# Top.net
KiCad netlist of a schematic drawn in Altium Designer
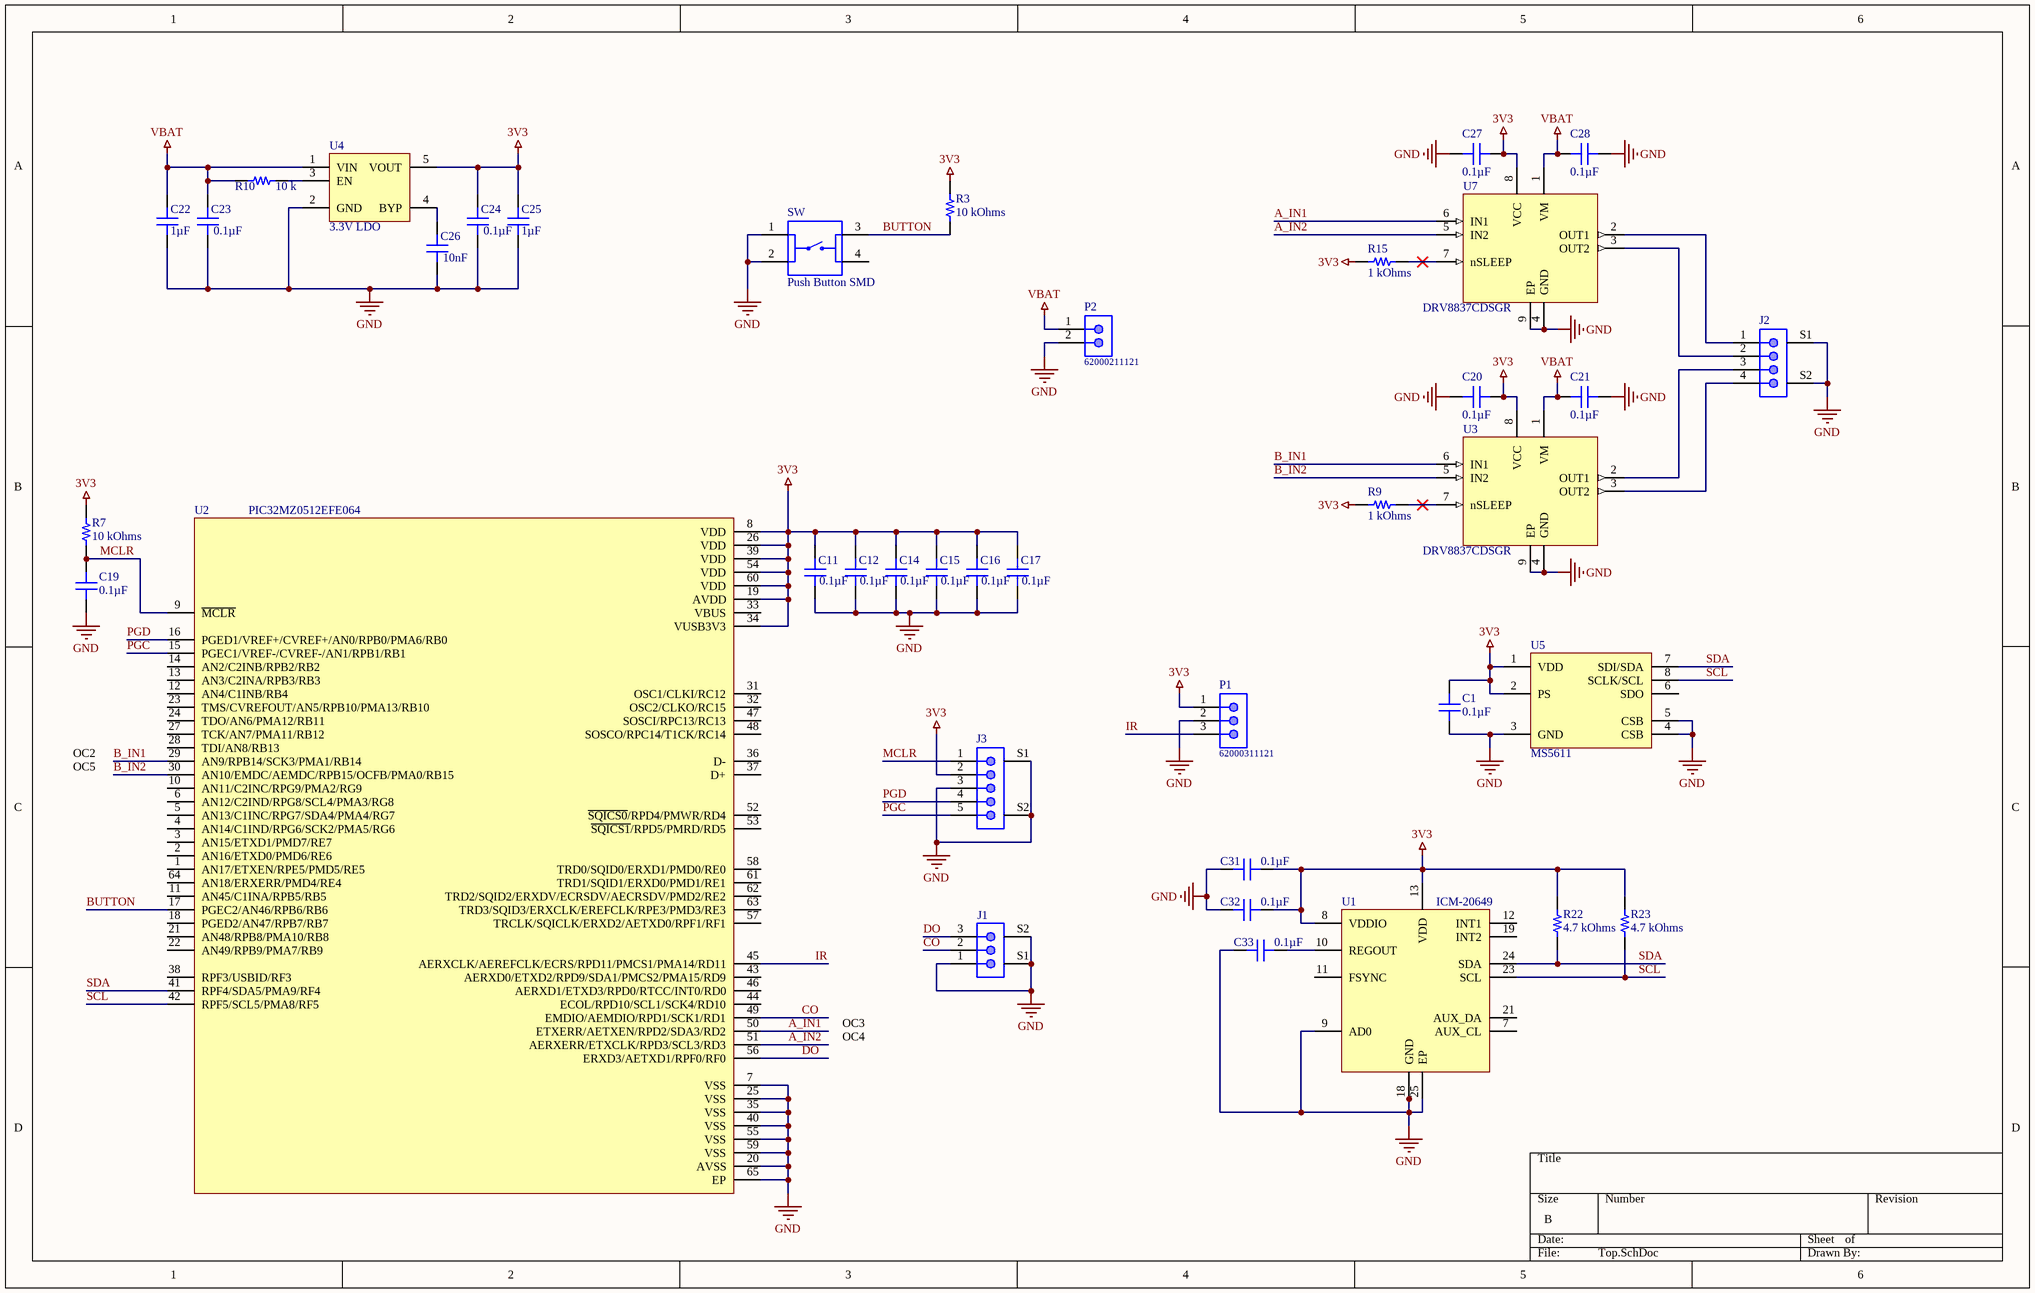
[diagram p0: Top.SchDoc]

(export (version "E")
  (design (tool "Eeschema 10.0.6"))
  (components
    (comp (ref "C1")
      (value "0.1µF")
      (footprint "CAP 0603_1608")
      (description "CAP CER 0.1UF 100V 0603 EPOXY")
      (fields
        (field (name "PART NUMBER") "GCG188R92A104KA03D")
        (field (name "MANUFACTURER") "Murata Electronics")
      )
      (libsource (lib "Celestial Altium Library - altium_library") (part "Capacitor"))
    )
    (comp (ref "C11")
      (value "0.1µF")
      (footprint "CAP 0603_1608")
      (description "CAP CER 0.1UF 100V 0603 EPOXY")
      (fields
        (field (name "PART NUMBER") "GCG188R92A104KA03D")
        (field (name "MANUFACTURER") "Murata Electronics")
      )
      (libsource (lib "Celestial Altium Library - altium_library") (part "Capacitor"))
    )
    (comp (ref "C12")
      (value "0.1µF")
      (footprint "CAP 0603_1608")
      (description "CAP CER 0.1UF 100V 0603 EPOXY")
      (fields
        (field (name "PART NUMBER") "GCG188R92A104KA03D")
        (field (name "MANUFACTURER") "Murata Electronics")
      )
      (libsource (lib "Celestial Altium Library - altium_library") (part "Capacitor"))
    )
    (comp (ref "C14")
      (value "0.1µF")
      (footprint "CAP 0603_1608")
      (description "CAP CER 0.1UF 100V 0603 EPOXY")
      (fields
        (field (name "PART NUMBER") "GCG188R92A104KA03D")
        (field (name "MANUFACTURER") "Murata Electronics")
      )
      (libsource (lib "Celestial Altium Library - altium_library") (part "Capacitor"))
    )
    (comp (ref "C15")
      (value "0.1µF")
      (footprint "CAP 0603_1608")
      (description "CAP CER 0.1UF 100V 0603 EPOXY")
      (fields
        (field (name "PART NUMBER") "GCG188R92A104KA03D")
        (field (name "MANUFACTURER") "Murata Electronics")
      )
      (libsource (lib "Celestial Altium Library - altium_library") (part "Capacitor"))
    )
    (comp (ref "C16")
      (value "0.1µF")
      (footprint "CAP 0603_1608")
      (description "CAP CER 0.1UF 100V 0603 EPOXY")
      (fields
        (field (name "PART NUMBER") "GCG188R92A104KA03D")
        (field (name "MANUFACTURER") "Murata Electronics")
      )
      (libsource (lib "Celestial Altium Library - altium_library") (part "Capacitor"))
    )
    (comp (ref "C17")
      (value "0.1µF")
      (footprint "CAP 0603_1608")
      (description "CAP CER 0.1UF 100V 0603 EPOXY")
      (fields
        (field (name "PART NUMBER") "GCG188R92A104KA03D")
        (field (name "MANUFACTURER") "Murata Electronics")
      )
      (libsource (lib "Celestial Altium Library - altium_library") (part "Capacitor"))
    )
    (comp (ref "C19")
      (value "0.1µF")
      (footprint "CAP 0603_1608")
      (description "CAP CER 0.1UF 100V 0603 EPOXY")
      (fields
        (field (name "PART NUMBER") "GCG188R92A104KA03D")
        (field (name "MANUFACTURER") "Murata Electronics")
      )
      (libsource (lib "Celestial Altium Library - altium_library") (part "Capacitor"))
    )
    (comp (ref "C20")
      (value "0.1µF")
      (footprint "CAP 0603_1608")
      (description "CAP CER 0.1UF 100V 0603 EPOXY")
      (fields
        (field (name "PART NUMBER") "GCG188R92A104KA03D")
        (field (name "MANUFACTURER") "Murata Electronics")
      )
      (libsource (lib "Celestial Altium Library - altium_library") (part "Capacitor"))
    )
    (comp (ref "C21")
      (value "0.1µF")
      (footprint "CAP 0603_1608")
      (description "CAP CER 0.1UF 100V 0603 EPOXY")
      (fields
        (field (name "PART NUMBER") "GCG188R92A104KA03D")
        (field (name "MANUFACTURER") "Murata Electronics")
      )
      (libsource (lib "Celestial Altium Library - altium_library") (part "Capacitor"))
    )
    (comp (ref "C22")
      (value "1µF")
      (footprint "CAP 0603_1608")
      (description "CAP CER 1UF 25V X7R 0603")
      (fields
        (field (name "PART NUMBER") "GCJ188R71E105KA01D")
        (field (name "MANUFACTURER") "Murata Electronics")
      )
      (libsource (lib "Celestial Altium Library - altium_library") (part "Capacitor"))
    )
    (comp (ref "C23")
      (value "0.1µF")
      (footprint "CAP 0603_1608")
      (description "CAP CER 0.1UF 100V 0603 EPOXY")
      (fields
        (field (name "PART NUMBER") "GCG188R92A104KA03D")
        (field (name "MANUFACTURER") "Murata Electronics")
      )
      (libsource (lib "Celestial Altium Library - altium_library") (part "Capacitor"))
    )
    (comp (ref "C24")
      (value "0.1µF")
      (footprint "CAP 0603_1608")
      (description "CAP CER 0.1UF 100V 0603 EPOXY")
      (fields
        (field (name "PART NUMBER") "GCG188R92A104KA03D")
        (field (name "MANUFACTURER") "Murata Electronics")
      )
      (libsource (lib "Celestial Altium Library - altium_library") (part "Capacitor"))
    )
    (comp (ref "C25")
      (value "1µF")
      (footprint "CAP 0603_1608")
      (description "CAP CER 1UF 25V X7R 0603")
      (fields
        (field (name "PART NUMBER") "GCJ188R71E105KA01D")
        (field (name "MANUFACTURER") "Murata Electronics")
      )
      (libsource (lib "Celestial Altium Library - altium_library") (part "Capacitor"))
    )
    (comp (ref "C26")
      (value "10nF")
      (footprint "CAP 0603_1608")
      (description "CAP CER 0.1UF 100V 0603 EPOXY")
      (fields
        (field (name "PART NUMBER") "GCG188R92A104KA03D")
        (field (name "MANUFACTURER") "Murata Electronics")
      )
      (libsource (lib "Celestial Altium Library - altium_library") (part "Capacitor"))
    )
    (comp (ref "C27")
      (value "0.1µF")
      (footprint "CAP 0603_1608")
      (description "CAP CER 0.1UF 100V 0603 EPOXY")
      (fields
        (field (name "PART NUMBER") "GCG188R92A104KA03D")
        (field (name "MANUFACTURER") "Murata Electronics")
      )
      (libsource (lib "Celestial Altium Library - altium_library") (part "Capacitor"))
    )
    (comp (ref "C28")
      (value "0.1µF")
      (footprint "CAP 0603_1608")
      (description "CAP CER 0.1UF 100V 0603 EPOXY")
      (fields
        (field (name "PART NUMBER") "GCG188R92A104KA03D")
        (field (name "MANUFACTURER") "Murata Electronics")
      )
      (libsource (lib "Celestial Altium Library - altium_library") (part "Capacitor"))
    )
    (comp (ref "C31")
      (value "0.1µF")
      (footprint "CAP 0603_1608")
      (description "CAP CER 0.1UF 100V 0603 EPOXY")
      (fields
        (field (name "PART NUMBER") "GCG188R92A104KA03D")
        (field (name "MANUFACTURER") "Murata Electronics")
      )
      (libsource (lib "Celestial Altium Library - altium_library") (part "Capacitor"))
    )
    (comp (ref "C32")
      (value "0.1µF")
      (footprint "CAP 0603_1608")
      (description "CAP CER 0.01UF 250V X7R 0603")
      (fields (field (name "PART NUMBER") "C0603C103KARACAUTO") (field (name "MANUFACTURER") "KEMET"))
      (libsource (lib "Celestial Altium Library - altium_library") (part "Capacitor"))
    )
    (comp (ref "C33")
      (value "0.1µF")
      (footprint "CAP 0603_1608")
      (description "CAP CER 0.1UF 100V 0603 EPOXY")
      (fields
        (field (name "PART NUMBER") "GCG188R92A104KA03D")
        (field (name "MANUFACTURER") "Murata Electronics")
      )
      (libsource (lib "Celestial Altium Library - altium_library") (part "Capacitor"))
    )
    (comp (ref "J1")
      (value "3 pos 0.8mm")
      (footprint "BM03B-SURS")
      (libsource (lib "IC") (part "BM03B-SURS"))
    )
    (comp (ref "J2")
      (value "4 pos 0.8mm")
      (footprint "BM04B-SURS")
      (libsource (lib "IC") (part "BM04B-SURS"))
    )
    (comp (ref "J3")
      (value "5 pos 0.8mm")
      (footprint "BM05B-SURS")
      (libsource (lib "IC") (part "BM05B-SURS"))
    )
    (comp (ref "P1")
      (value "62000311121")
      (footprint "62000311121")
      (description "WR-PHD Pin Header, THT, pitch 2mm, Single Row, Vertical, 3p")
      (fields (field (name "MANUFACTURER") "Wurth Elektronik"))
      (libsource (lib "Altium_WR-PHD") (part "62000311121"))
    )
    (comp (ref "P2")
      (value "62000211121")
      (footprint "62000211121")
      (description "WR-PHD Pin Header, THT, pitch 2mm, Single Row, Vertical, 2p")
      (fields (field (name "MANUFACTURER") "Wurth Elektronik"))
      (libsource (lib "Altium_WR-PHD") (part "62000211121"))
    )
    (comp (ref "R3")
      (value "10 kOhms")
      (footprint "RES 0603_1608")
      (description "RES SMD 1K OHM 1% 1/10W 0603")
      (fields (field (name "PART NUMBER") "RT0603FRE071KL") (field (name "MANUFACTURER") "Yageo"))
      (libsource (lib "Celestial Altium Library - altium_library") (part "Resistor"))
    )
    (comp (ref "R7")
      (value "10 kOhms")
      (footprint "RES 0603_1608")
      (description "RES 10K OHM 0.1% 1/16W 0603")
      (fields
        (field (name "PART NUMBER") "RNCS0603BKE10K0")
        (field (name "MANUFACTURER") "Stackpole Electronics Inc")
      )
      (libsource (lib "Celestial Altium Library - altium_library") (part "Resistor"))
    )
    (comp (ref "R9")
      (value "1 kOhms")
      (footprint "RES 0603_1608")
      (description "RES SMD 1K OHM 1% 1/10W 0603")
      (fields (field (name "PART NUMBER") "RT0603FRE071KL") (field (name "MANUFACTURER") "Yageo"))
      (libsource (lib "Celestial Altium Library - altium_library") (part "Resistor"))
    )
    (comp (ref "R10")
      (value "10 k")
      (footprint "RES 0603_1608")
      (description "RES 10K OHM 0.1% 1/16W 0603")
      (fields
        (field (name "PART NUMBER") "RNCS0603BKE10K0")
        (field (name "MANUFACTURER") "Stackpole Electronics Inc")
      )
      (libsource (lib "Celestial Altium Library - altium_library") (part "Resistor"))
    )
    (comp (ref "R15")
      (value "1 kOhms")
      (footprint "RES 0603_1608")
      (description "RES SMD 1K OHM 1% 1/10W 0603")
      (fields (field (name "PART NUMBER") "RT0603FRE071KL") (field (name "MANUFACTURER") "Yageo"))
      (libsource (lib "Celestial Altium Library - altium_library") (part "Resistor"))
    )
    (comp (ref "R22")
      (value "4.7 kOhms")
      (footprint "RES 0603_1608")
      (description "RES SMD 4.7K OHM 0.1% 1/16W 0603")
      (fields
        (field (name "PART NUMBER") "CPF-A-0603B4K7E")
        (field (name "MANUFACTURER") "TE Connectivity Passive Product")
      )
      (libsource (lib "Celestial Altium Library - altium_library") (part "Resistor"))
    )
    (comp (ref "R23")
      (value "4.7 kOhms")
      (footprint "RES 0603_1608")
      (description "RES SMD 4.7K OHM 0.1% 1/16W 0603")
      (fields
        (field (name "PART NUMBER") "CPF-A-0603B4K7E")
        (field (name "MANUFACTURER") "TE Connectivity Passive Product")
      )
      (libsource (lib "Celestial Altium Library - altium_library") (part "Resistor"))
    )
    (comp (ref "SW")
      (value "Push Button SMD")
      (footprint "SMD button")
      (description "50 mA SPST Round Actuator 160 Gram Force Tactile Pushbutton Switch")
      (fields (field (name "MP") "1825910-2") (field (name "MF") "TE Connectivity"))
      (libsource (lib "IC") (part "Push Button SMD"))
    )
    (comp (ref "U1")
      (value "ICM-20649")
      (footprint "ICM-20649")
      (description "6-DOF IMU")
      (libsource (lib "IC") (part "ICM-20649"))
    )
    (comp (ref "U2")
      (value "PIC32MZ0512EFE064")
      (footprint "QFN50P900X900X100-65N")
      (description "32-bit Microcontrollers - MCU 32-BIT MCU 512KB FL 128KB RAM, No Crypto")
      (fields (field (name "MF") "Microchip") (field (name "MP") "PIC32MZ2048EFG064T-I/PT"))
      (libsource (lib "IC") (part "PIC32MZ0512EFE064-I/PT"))
    )
    (comp (ref "U3")
      (value "DRV8837CDSGR")
      (footprint "SON50P200X200X80-9N")
      (description "11-V, 1-A H-bridge motor driver 8-WSON -40 to 85")
      (fields (field (name "MF") "Texas Instruments"))
      (libsource (lib "IC") (part "DRV8837CDSGR"))
    )
    (comp (ref "U4")
      (value "3.3V LDO")
      (footprint "TI SOT-23-5 DBV")
      (libsource (lib "IC") (part "MIC5504-3.3YM5"))
    )
    (comp (ref "U5")
      (value "MS5611")
      (footprint "MS5611")
      (description "Altimeter")
      (libsource (lib "IC") (part "MS5611"))
    )
    (comp (ref "U7")
      (value "DRV8837CDSGR")
      (footprint "SON50P200X200X80-9N")
      (description "11-V, 1-A H-bridge motor driver 8-WSON -40 to 85")
      (fields (field (name "MF") "Texas Instruments"))
      (libsource (lib "IC") (part "DRV8837CDSGR"))
    )
  )
  (nets
    (net (code "1") (name "/A_IN1") (class "Default")
      (node (ref "U2") (pin "50") (pinfunction "ETXERR/AETXEN/RPD2/SDA3/RD2_50") (pintype "passive"))
      (node (ref "U7") (pin "6") (pinfunction "IN1_6") (pintype "input"))
    )
    (net (code "2") (name "/A_IN2") (class "Default")
      (node (ref "U2") (pin "51") (pinfunction "AERXERR/ETXCLK/RPD3/SCL3/RD3_51") (pintype "passive"))
      (node (ref "U7") (pin "5") (pinfunction "IN2_5") (pintype "input"))
    )
    (net (code "3") (name "/BUTTON") (class "Default")
      (node (ref "R3") (pin "2") (pinfunction "2_2") (pintype "passive"))
      (node (ref "SW") (pin "3") (pinfunction "3_3") (pintype "passive"))
      (node (ref "U2") (pin "17") (pinfunction "PGEC2/AN46/RPB6/RB6_17") (pintype "passive"))
    )
    (net (code "4") (name "/B_IN1") (class "Default")
      (node (ref "U2") (pin "29") (pinfunction "AN9/RPB14/SCK3/PMA1/RB14_29") (pintype "passive"))
      (node (ref "U3") (pin "6") (pinfunction "IN1_6") (pintype "input"))
    )
    (net (code "5") (name "/B_IN2") (class "Default")
      (node (ref "U2") (pin "30") (pinfunction "AN10/EMDC/AEMDC/RPB15/OCFB/PMA0/RB15_30") (pintype "passive"))
      (node (ref "U3") (pin "5") (pinfunction "IN2_5") (pintype "input"))
    )
    (net (code "6") (name "/CO") (class "Default")
      (node (ref "J1") (pin "2") (pinfunction "2_2") (pintype "passive"))
      (node (ref "U2") (pin "49") (pinfunction "EMDIO/AEMDIO/RPD1/SCK1/RD1_49") (pintype "passive"))
    )
    (net (code "7") (name "/DO") (class "Default")
      (node (ref "J1") (pin "3") (pinfunction "1_3") (pintype "passive"))
      (node (ref "U2") (pin "56") (pinfunction "ERXD3/AETXD1/RPF0/RF0_56") (pintype "passive"))
    )
    (net (code "8") (name "/IR") (class "Default")
      (node (ref "P1") (pin "3") (pinfunction "3_3") (pintype "passive"))
      (node (ref "U2") (pin "45") (pinfunction "AERXCLK/AEREFCLK/ECRS/RPD11/PMCS1/PMA14/RD11_45") (pintype "passive"))
    )
    (net (code "9") (name "/MCLR") (class "Default")
      (node (ref "C19") (pin "1") (pinfunction "1_1") (pintype "passive"))
      (node (ref "J3") (pin "1") (pinfunction "1_1") (pintype "passive"))
      (node (ref "R7") (pin "1") (pinfunction "1_1") (pintype "passive"))
      (node (ref "U2") (pin "9") (pinfunction "~{MCLR}_9") (pintype "passive"))
    )
    (net (code "10") (name "/PGC") (class "Default")
      (node (ref "J3") (pin "5") (pinfunction "2_5") (pintype "passive"))
      (node (ref "U2") (pin "15") (pinfunction "PGEC1/VREF-/CVREF-/AN1/RPB1/RB1_15") (pintype "passive"))
    )
    (net (code "11") (name "/PGD") (class "Default")
      (node (ref "J3") (pin "4") (pinfunction "2_4") (pintype "passive"))
      (node (ref "U2") (pin "16") (pinfunction "PGED1/VREF+/CVREF+/AN0/RPB0/PMA6/RB0_16") (pintype "passive"))
    )
    (net (code "12") (name "/SCL") (class "Default")
      (node (ref "R23") (pin "1") (pinfunction "1_1") (pintype "passive"))
      (node (ref "U1") (pin "23") (pinfunction "SCL_23") (pintype "passive"))
      (node (ref "U2") (pin "42") (pinfunction "RPF5/SCL5/PMA8/RF5_42") (pintype "passive"))
      (node (ref "U5") (pin "8") (pinfunction "SCLK/SCL_8") (pintype "passive"))
    )
    (net (code "13") (name "/SDA") (class "Default")
      (node (ref "R22") (pin "1") (pinfunction "1_1") (pintype "passive"))
      (node (ref "U1") (pin "24") (pinfunction "SDA_24") (pintype "passive"))
      (node (ref "U2") (pin "41") (pinfunction "RPF4/SDA5/PMA9/RF4_41") (pintype "passive"))
      (node (ref "U5") (pin "7") (pinfunction "SDI/SDA_7") (pintype "passive"))
    )
    (net (code "14") (name "3V3") (class "Default")
      (node (ref "C1") (pin "2") (pinfunction "2_2") (pintype "passive"))
      (node (ref "C11") (pin "1") (pinfunction "1_1") (pintype "passive"))
      (node (ref "C12") (pin "1") (pinfunction "1_1") (pintype "passive"))
      (node (ref "C14") (pin "1") (pinfunction "1_1") (pintype "passive"))
      (node (ref "C15") (pin "1") (pinfunction "1_1") (pintype "passive"))
      (node (ref "C16") (pin "1") (pinfunction "1_1") (pintype "passive"))
      (node (ref "C17") (pin "1") (pinfunction "1_1") (pintype "passive"))
      (node (ref "C20") (pin "2") (pinfunction "2_2") (pintype "passive"))
      (node (ref "C24") (pin "1") (pinfunction "1_1") (pintype "passive"))
      (node (ref "C25") (pin "2") (pinfunction "2_2") (pintype "passive"))
      (node (ref "C27") (pin "2") (pinfunction "2_2") (pintype "passive"))
      (node (ref "C31") (pin "2") (pinfunction "2_2") (pintype "passive"))
      (node (ref "C32") (pin "2") (pinfunction "2_2") (pintype "passive"))
      (node (ref "J3") (pin "2") (pinfunction "2_2") (pintype "passive"))
      (node (ref "P1") (pin "1") (pinfunction "1_1") (pintype "passive"))
      (node (ref "R15") (pin "2") (pinfunction "2_2") (pintype "passive"))
      (node (ref "R22") (pin "2") (pinfunction "2_2") (pintype "passive"))
      (node (ref "R23") (pin "2") (pinfunction "2_2") (pintype "passive"))
      (node (ref "R3") (pin "1") (pinfunction "1_1") (pintype "passive"))
      (node (ref "R7") (pin "2") (pinfunction "2_2") (pintype "passive"))
      (node (ref "R9") (pin "2") (pinfunction "2_2") (pintype "passive"))
      (node (ref "U1") (pin "13") (pinfunction "VDD_13") (pintype "passive"))
      (node (ref "U1") (pin "8") (pinfunction "VDDIO_8") (pintype "passive"))
      (node (ref "U2") (pin "19") (pinfunction "AVDD_19") (pintype "power_in"))
      (node (ref "U2") (pin "26") (pinfunction "VDD_26") (pintype "power_in"))
      (node (ref "U2") (pin "34") (pinfunction "VUSB3V3_34") (pintype "power_in"))
      (node (ref "U2") (pin "39") (pinfunction "VDD_39") (pintype "power_in"))
      (node (ref "U2") (pin "54") (pinfunction "VDD_54") (pintype "power_in"))
      (node (ref "U2") (pin "60") (pinfunction "VDD_60") (pintype "power_in"))
      (node (ref "U2") (pin "8") (pinfunction "VDD_8") (pintype "power_in"))
      (node (ref "U3") (pin "8") (pinfunction "VCC_8") (pintype "power_in"))
      (node (ref "U4") (pin "5") (pinfunction "VOUT_5") (pintype "passive"))
      (node (ref "U5") (pin "1") (pinfunction "VDD_1") (pintype "passive"))
      (node (ref "U5") (pin "2") (pinfunction "PS_2") (pintype "passive"))
      (node (ref "U7") (pin "8") (pinfunction "VCC_8") (pintype "power_in"))
    )
    (net (code "15") (name "GND") (class "Default")
      (node (ref "C1") (pin "1") (pinfunction "1_1") (pintype "passive"))
      (node (ref "C11") (pin "2") (pinfunction "2_2") (pintype "passive"))
      (node (ref "C12") (pin "2") (pinfunction "2_2") (pintype "passive"))
      (node (ref "C14") (pin "2") (pinfunction "2_2") (pintype "passive"))
      (node (ref "C15") (pin "2") (pinfunction "2_2") (pintype "passive"))
      (node (ref "C16") (pin "2") (pinfunction "2_2") (pintype "passive"))
      (node (ref "C17") (pin "2") (pinfunction "2_2") (pintype "passive"))
      (node (ref "C19") (pin "2") (pinfunction "2_2") (pintype "passive"))
      (node (ref "C20") (pin "1") (pinfunction "1_1") (pintype "passive"))
      (node (ref "C21") (pin "2") (pinfunction "2_2") (pintype "passive"))
      (node (ref "C22") (pin "1") (pinfunction "1_1") (pintype "passive"))
      (node (ref "C23") (pin "2") (pinfunction "2_2") (pintype "passive"))
      (node (ref "C24") (pin "2") (pinfunction "2_2") (pintype "passive"))
      (node (ref "C25") (pin "1") (pinfunction "1_1") (pintype "passive"))
      (node (ref "C26") (pin "2") (pinfunction "2_2") (pintype "passive"))
      (node (ref "C27") (pin "1") (pinfunction "1_1") (pintype "passive"))
      (node (ref "C28") (pin "2") (pinfunction "2_2") (pintype "passive"))
      (node (ref "C31") (pin "1") (pinfunction "1_1") (pintype "passive"))
      (node (ref "C32") (pin "1") (pinfunction "1_1") (pintype "passive"))
      (node (ref "C33") (pin "2") (pinfunction "2_2") (pintype "passive"))
      (node (ref "J1") (pin "1") (pinfunction "1_1") (pintype "passive"))
      (node (ref "J1") (pin "S1") (pinfunction "1_S1") (pintype "passive"))
      (node (ref "J1") (pin "S2") (pinfunction "2_S2") (pintype "passive"))
      (node (ref "J2") (pin "S1") (pinfunction "1_S1") (pintype "passive"))
      (node (ref "J2") (pin "S2") (pinfunction "2_S2") (pintype "passive"))
      (node (ref "J3") (pin "3") (pinfunction "1_3") (pintype "passive"))
      (node (ref "J3") (pin "S1") (pinfunction "1_S1") (pintype "passive"))
      (node (ref "J3") (pin "S2") (pinfunction "2_S2") (pintype "passive"))
      (node (ref "P1") (pin "2") (pinfunction "2_2") (pintype "passive"))
      (node (ref "P2") (pin "2") (pinfunction "2_2") (pintype "passive"))
      (node (ref "SW") (pin "1") (pinfunction "1_1") (pintype "passive"))
      (node (ref "SW") (pin "2") (pinfunction "2_2") (pintype "passive"))
      (node (ref "U1") (pin "18") (pinfunction "GND_18") (pintype "passive"))
      (node (ref "U1") (pin "20") (pinfunction "RESV_20") (pintype "passive"))
      (node (ref "U1") (pin "25") (pinfunction "EP_25") (pintype "passive"))
      (node (ref "U1") (pin "9") (pinfunction "AD0_9") (pintype "passive"))
      (node (ref "U2") (pin "20") (pinfunction "AVSS_20") (pintype "power_in"))
      (node (ref "U2") (pin "25") (pinfunction "VSS_25") (pintype "power_in"))
      (node (ref "U2") (pin "35") (pinfunction "VSS_35") (pintype "power_in"))
      (node (ref "U2") (pin "40") (pinfunction "VSS_40") (pintype "power_in"))
      (node (ref "U2") (pin "55") (pinfunction "VSS_55") (pintype "power_in"))
      (node (ref "U2") (pin "59") (pinfunction "VSS_59") (pintype "power_in"))
      (node (ref "U2") (pin "65") (pinfunction "EP_65") (pintype "power_in"))
      (node (ref "U2") (pin "7") (pinfunction "VSS_7") (pintype "power_in"))
      (node (ref "U3") (pin "4") (pinfunction "GND_4") (pintype "power_in"))
      (node (ref "U3") (pin "9") (pinfunction "EP_9") (pintype "power_in"))
      (node (ref "U4") (pin "2") (pinfunction "GND_2") (pintype "passive"))
      (node (ref "U5") (pin "3") (pinfunction "GND_3") (pintype "passive"))
      (node (ref "U5") (pin "4") (pinfunction "CSB_4") (pintype "passive"))
      (node (ref "U5") (pin "5") (pinfunction "CSB_5") (pintype "passive"))
      (node (ref "U7") (pin "4") (pinfunction "GND_4") (pintype "power_in"))
      (node (ref "U7") (pin "9") (pinfunction "EP_9") (pintype "power_in"))
    )
    (net (code "16") (name "Net-(U1-REGOUT)") (class "Default")
      (node (ref "C33") (pin "1") (pinfunction "1_1") (pintype "passive"))
      (node (ref "U1") (pin "10") (pinfunction "REGOUT_10") (pintype "passive"))
    )
    (net (code "17") (name "Net-(U3-OUT1)") (class "Default")
      (node (ref "J2") (pin "3") (pinfunction "1_3") (pintype "passive"))
      (node (ref "U3") (pin "2") (pinfunction "OUT1_2") (pintype "output"))
    )
    (net (code "18") (name "Net-(U3-OUT2)") (class "Default")
      (node (ref "J2") (pin "4") (pinfunction "2_4") (pintype "passive"))
      (node (ref "U3") (pin "3") (pinfunction "OUT2_3") (pintype "output"))
    )
    (net (code "19") (name "Net-(U3-nSLEEP)") (class "Default")
      (node (ref "R9") (pin "1") (pinfunction "1_1") (pintype "passive"))
      (node (ref "U3") (pin "7") (pinfunction "nSLEEP_7") (pintype "input"))
    )
    (net (code "20") (name "Net-(U4-BYP)") (class "Default")
      (node (ref "C26") (pin "1") (pinfunction "1_1") (pintype "passive"))
      (node (ref "U4") (pin "4") (pinfunction "BYP_4") (pintype "passive"))
    )
    (net (code "21") (name "Net-(U4-EN)") (class "Default")
      (node (ref "R10") (pin "1") (pinfunction "1_1") (pintype "passive"))
      (node (ref "U4") (pin "3") (pinfunction "EN_3") (pintype "passive"))
    )
    (net (code "22") (name "Net-(U7-OUT1)") (class "Default")
      (node (ref "J2") (pin "1") (pinfunction "1_1") (pintype "passive"))
      (node (ref "U7") (pin "2") (pinfunction "OUT1_2") (pintype "output"))
    )
    (net (code "23") (name "Net-(U7-OUT2)") (class "Default")
      (node (ref "J2") (pin "2") (pinfunction "2_2") (pintype "passive"))
      (node (ref "U7") (pin "3") (pinfunction "OUT2_3") (pintype "output"))
    )
    (net (code "24") (name "Net-(U7-nSLEEP)") (class "Default")
      (node (ref "R15") (pin "1") (pinfunction "1_1") (pintype "passive"))
      (node (ref "U7") (pin "7") (pinfunction "nSLEEP_7") (pintype "input"))
    )
    (net (code "25") (name "VBAT") (class "Default")
      (node (ref "C21") (pin "1") (pinfunction "1_1") (pintype "passive"))
      (node (ref "C22") (pin "2") (pinfunction "2_2") (pintype "passive"))
      (node (ref "C23") (pin "1") (pinfunction "1_1") (pintype "passive"))
      (node (ref "C28") (pin "1") (pinfunction "1_1") (pintype "passive"))
      (node (ref "P2") (pin "1") (pinfunction "1_1") (pintype "passive"))
      (node (ref "R10") (pin "2") (pinfunction "2_2") (pintype "passive"))
      (node (ref "U3") (pin "1") (pinfunction "VM_1") (pintype "power_in"))
      (node (ref "U4") (pin "1") (pinfunction "VIN_1") (pintype "passive"))
      (node (ref "U7") (pin "1") (pinfunction "VM_1") (pintype "power_in"))
    )
    (net (code "26") (name "unconnected-(SW-Pad4)") (class "Default")
      (node (ref "SW") (pin "4") (pinfunction "4_4") (pintype "passive"))
    )
    (net (code "27") (name "unconnected-(U1-AUX_CL-Pad7)") (class "Default")
      (node (ref "U1") (pin "7") (pinfunction "AUX_CL_7") (pintype "passive"))
    )
    (net (code "28") (name "unconnected-(U1-AUX_DA-Pad21)") (class "Default")
      (node (ref "U1") (pin "21") (pinfunction "AUX_DA_21") (pintype "passive"))
    )
    (net (code "29") (name "unconnected-(U1-FSYNC-Pad11)") (class "Default")
      (node (ref "U1") (pin "11") (pinfunction "FSYNC_11") (pintype "passive"))
    )
    (net (code "30") (name "unconnected-(U1-INT1-Pad12)") (class "Default")
      (node (ref "U1") (pin "12") (pinfunction "INT1_12") (pintype "passive"))
    )
    (net (code "31") (name "unconnected-(U1-INT2-Pad19)") (class "Default")
      (node (ref "U1") (pin "19") (pinfunction "INT2_19") (pintype "passive"))
    )
    (net (code "32") (name "unconnected-(U2-AERXD0{slash}ETXD2{slash}RPD9{slash}SDA1{slash}PMCS2{slash}PMA15{slash}RD9-Pad43)") (class "Default")
      (node (ref "U2") (pin "43") (pinfunction "AERXD0/ETXD2/RPD9/SDA1/PMCS2/PMA15/RD9_43") (pintype "passive"))
    )
    (net (code "33") (name "unconnected-(U2-AERXD1{slash}ETXD3{slash}RPD0{slash}RTCC{slash}INT0{slash}RD0-Pad46)") (class "Default")
      (node (ref "U2") (pin "46") (pinfunction "AERXD1/ETXD3/RPD0/RTCC/INT0/RD0_46") (pintype "passive"))
    )
    (net (code "34") (name "unconnected-(U2-AN2{slash}C2INB{slash}RPB2{slash}RB2-Pad14)") (class "Default")
      (node (ref "U2") (pin "14") (pinfunction "AN2/C2INB/RPB2/RB2_14") (pintype "passive"))
    )
    (net (code "35") (name "unconnected-(U2-AN3{slash}C2INA{slash}RPB3{slash}RB3-Pad13)") (class "Default")
      (node (ref "U2") (pin "13") (pinfunction "AN3/C2INA/RPB3/RB3_13") (pintype "passive"))
    )
    (net (code "36") (name "unconnected-(U2-AN4{slash}C1INB{slash}RB4-Pad12)") (class "Default")
      (node (ref "U2") (pin "12") (pinfunction "AN4/C1INB/RB4_12") (pintype "passive"))
    )
    (net (code "37") (name "unconnected-(U2-AN11{slash}C2INC{slash}RPG9{slash}PMA2{slash}RG9-Pad10)") (class "Default")
      (node (ref "U2") (pin "10") (pinfunction "AN11/C2INC/RPG9/PMA2/RG9_10") (pintype "passive"))
    )
    (net (code "38") (name "unconnected-(U2-AN12{slash}C2IND{slash}RPG8{slash}SCL4{slash}PMA3{slash}RG8-Pad6)") (class "Default")
      (node (ref "U2") (pin "6") (pinfunction "AN12/C2IND/RPG8/SCL4/PMA3/RG8_6") (pintype "passive"))
    )
    (net (code "39") (name "unconnected-(U2-AN13{slash}C1INC{slash}RPG7{slash}SDA4{slash}PMA4{slash}RG7-Pad5)") (class "Default")
      (node (ref "U2") (pin "5") (pinfunction "AN13/C1INC/RPG7/SDA4/PMA4/RG7_5") (pintype "passive"))
    )
    (net (code "40") (name "unconnected-(U2-AN14{slash}C1IND{slash}RPG6{slash}SCK2{slash}PMA5{slash}RG6-Pad4)") (class "Default")
      (node (ref "U2") (pin "4") (pinfunction "AN14/C1IND/RPG6/SCK2/PMA5/RG6_4") (pintype "passive"))
    )
    (net (code "41") (name "unconnected-(U2-AN15{slash}ETXD1{slash}PMD7{slash}RE7-Pad3)") (class "Default")
      (node (ref "U2") (pin "3") (pinfunction "AN15/ETXD1/PMD7/RE7_3") (pintype "passive"))
    )
    (net (code "42") (name "unconnected-(U2-AN16{slash}ETXD0{slash}PMD6{slash}RE6-Pad2)") (class "Default")
      (node (ref "U2") (pin "2") (pinfunction "AN16/ETXD0/PMD6/RE6_2") (pintype "passive"))
    )
    (net (code "43") (name "unconnected-(U2-AN17{slash}ETXEN{slash}RPE5{slash}PMD5{slash}RE5-Pad1)") (class "Default")
      (node (ref "U2") (pin "1") (pinfunction "AN17/ETXEN/RPE5/PMD5/RE5_1") (pintype "passive"))
    )
    (net (code "44") (name "unconnected-(U2-AN18{slash}ERXERR{slash}PMD4{slash}RE4-Pad64)") (class "Default")
      (node (ref "U2") (pin "64") (pinfunction "AN18/ERXERR/PMD4/RE4_64") (pintype "passive"))
    )
    (net (code "45") (name "unconnected-(U2-AN45{slash}C1INA{slash}RPB5{slash}RB5-Pad11)") (class "Default")
      (node (ref "U2") (pin "11") (pinfunction "AN45/C1INA/RPB5/RB5_11") (pintype "passive"))
    )
    (net (code "46") (name "unconnected-(U2-AN48{slash}RPB8{slash}PMA10{slash}RB8-Pad21)") (class "Default")
      (node (ref "U2") (pin "21") (pinfunction "AN48/RPB8/PMA10/RB8_21") (pintype "passive"))
    )
    (net (code "47") (name "unconnected-(U2-AN49{slash}RPB9{slash}PMA7{slash}RB9-Pad22)") (class "Default")
      (node (ref "U2") (pin "22") (pinfunction "AN49/RPB9/PMA7/RB9_22") (pintype "passive"))
    )
    (net (code "48") (name "unconnected-(U2-D+-Pad37)") (class "Default")
      (node (ref "U2") (pin "37") (pinfunction "D+_37") (pintype "passive"))
    )
    (net (code "49") (name "unconnected-(U2-D--Pad36)") (class "Default")
      (node (ref "U2") (pin "36") (pinfunction "D-_36") (pintype "passive"))
    )
    (net (code "50") (name "unconnected-(U2-ECOL{slash}RPD10{slash}SCL1{slash}SCK4{slash}RD10-Pad44)") (class "Default")
      (node (ref "U2") (pin "44") (pinfunction "ECOL/RPD10/SCL1/SCK4/RD10_44") (pintype "passive"))
    )
    (net (code "51") (name "unconnected-(U2-OSC1{slash}CLKI{slash}RC12-Pad31)") (class "Default")
      (node (ref "U2") (pin "31") (pinfunction "OSC1/CLKI/RC12_31") (pintype "passive"))
    )
    (net (code "52") (name "unconnected-(U2-OSC2{slash}CLKO{slash}RC15-Pad32)") (class "Default")
      (node (ref "U2") (pin "32") (pinfunction "OSC2/CLKO/RC15_32") (pintype "passive"))
    )
    (net (code "53") (name "unconnected-(U2-PGED2{slash}AN47{slash}RPB7{slash}RB7-Pad18)") (class "Default")
      (node (ref "U2") (pin "18") (pinfunction "PGED2/AN47/RPB7/RB7_18") (pintype "passive"))
    )
    (net (code "54") (name "unconnected-(U2-RPF3{slash}USBID{slash}RF3-Pad38)") (class "Default")
      (node (ref "U2") (pin "38") (pinfunction "RPF3/USBID/RF3_38") (pintype "passive"))
    )
    (net (code "55") (name "unconnected-(U2-SOSCI{slash}RPC13{slash}RC13-Pad47)") (class "Default")
      (node (ref "U2") (pin "47") (pinfunction "SOSCI/RPC13/RC13_47") (pintype "passive"))
    )
    (net (code "56") (name "unconnected-(U2-SOSCO{slash}RPC14{slash}T1CK{slash}RC14-Pad48)") (class "Default")
      (node (ref "U2") (pin "48") (pinfunction "SOSCO/RPC14/T1CK/RC14_48") (pintype "passive"))
    )
    (net (code "57") (name "unconnected-(U2-TCK{slash}AN7{slash}PMA11{slash}RB12-Pad27)") (class "Default")
      (node (ref "U2") (pin "27") (pinfunction "TCK/AN7/PMA11/RB12_27") (pintype "passive"))
    )
    (net (code "58") (name "unconnected-(U2-TDI{slash}AN8{slash}RB13-Pad28)") (class "Default")
      (node (ref "U2") (pin "28") (pinfunction "TDI/AN8/RB13_28") (pintype "passive"))
    )
    (net (code "59") (name "unconnected-(U2-TDO{slash}AN6{slash}PMA12{slash}RB11-Pad24)") (class "Default")
      (node (ref "U2") (pin "24") (pinfunction "TDO/AN6/PMA12/RB11_24") (pintype "passive"))
    )
    (net (code "60") (name "unconnected-(U2-TMS{slash}CVREFOUT{slash}AN5{slash}RPB10{slash}PMA13{slash}RB10-Pad23)") (class "Default")
      (node (ref "U2") (pin "23") (pinfunction "TMS/CVREFOUT/AN5/RPB10/PMA13/RB10_23") (pintype "passive"))
    )
    (net (code "61") (name "unconnected-(U2-TRCLK{slash}SQICLK{slash}ERXD2{slash}AETXD0{slash}RPF1{slash}RF1-Pad57)") (class "Default")
      (node (ref "U2") (pin "57") (pinfunction "TRCLK/SQICLK/ERXD2/AETXD0/RPF1/RF1_57") (pintype "passive"))
    )
    (net (code "62") (name "unconnected-(U2-TRD0{slash}SQID0{slash}ERXD1{slash}PMD0{slash}RE0-Pad58)") (class "Default")
      (node (ref "U2") (pin "58") (pinfunction "TRD0/SQID0/ERXD1/PMD0/RE0_58") (pintype "passive"))
    )
    (net (code "63") (name "unconnected-(U2-TRD1{slash}SQID1{slash}ERXD0{slash}PMD1{slash}RE1-Pad61)") (class "Default")
      (node (ref "U2") (pin "61") (pinfunction "TRD1/SQID1/ERXD0/PMD1/RE1_61") (pintype "passive"))
    )
    (net (code "64") (name "unconnected-(U2-TRD2{slash}SQID2{slash}ERXDV{slash}ECRSDV{slash}AECRSDV{slash}PMD2{slash}RE2-Pad62)") (class "Default")
      (node (ref "U2") (pin "62") (pinfunction "TRD2/SQID2/ERXDV/ECRSDV/AECRSDV/PMD2/RE2_62") (pintype "passive"))
    )
    (net (code "65") (name "unconnected-(U2-TRD3{slash}SQID3{slash}ERXCLK{slash}EREFCLK{slash}RPE3{slash}PMD3{slash}RE3-Pad63)") (class "Default")
      (node (ref "U2") (pin "63") (pinfunction "TRD3/SQID3/ERXCLK/EREFCLK/RPE3/PMD3/RE3_63") (pintype "passive"))
    )
    (net (code "66") (name "unconnected-(U2-VBUS-Pad33)") (class "Default")
      (node (ref "U2") (pin "33") (pinfunction "VBUS_33") (pintype "power_in"))
    )
    (net (code "67") (name "unconnected-(U2-~{SQICS0}{slash}RPD4{slash}PMWR{slash}RD4-Pad52)") (class "Default")
      (node (ref "U2") (pin "52") (pinfunction "~{SQICS0}/RPD4/PMWR/RD4_52") (pintype "passive"))
    )
    (net (code "68") (name "unconnected-(U2-~{SQICS1}{slash}RPD5{slash}PMRD{slash}RD5-Pad53)") (class "Default")
      (node (ref "U2") (pin "53") (pinfunction "~{SQICS1}/RPD5/PMRD/RD5_53") (pintype "passive"))
    )
    (net (code "69") (name "unconnected-(U5-SDO-Pad6)") (class "Default")
      (node (ref "U5") (pin "6") (pinfunction "SDO_6") (pintype "passive"))
    )
  )
)
